# I2C_CH2.net
KiCad netlist of a schematic drawn in Altium Designer
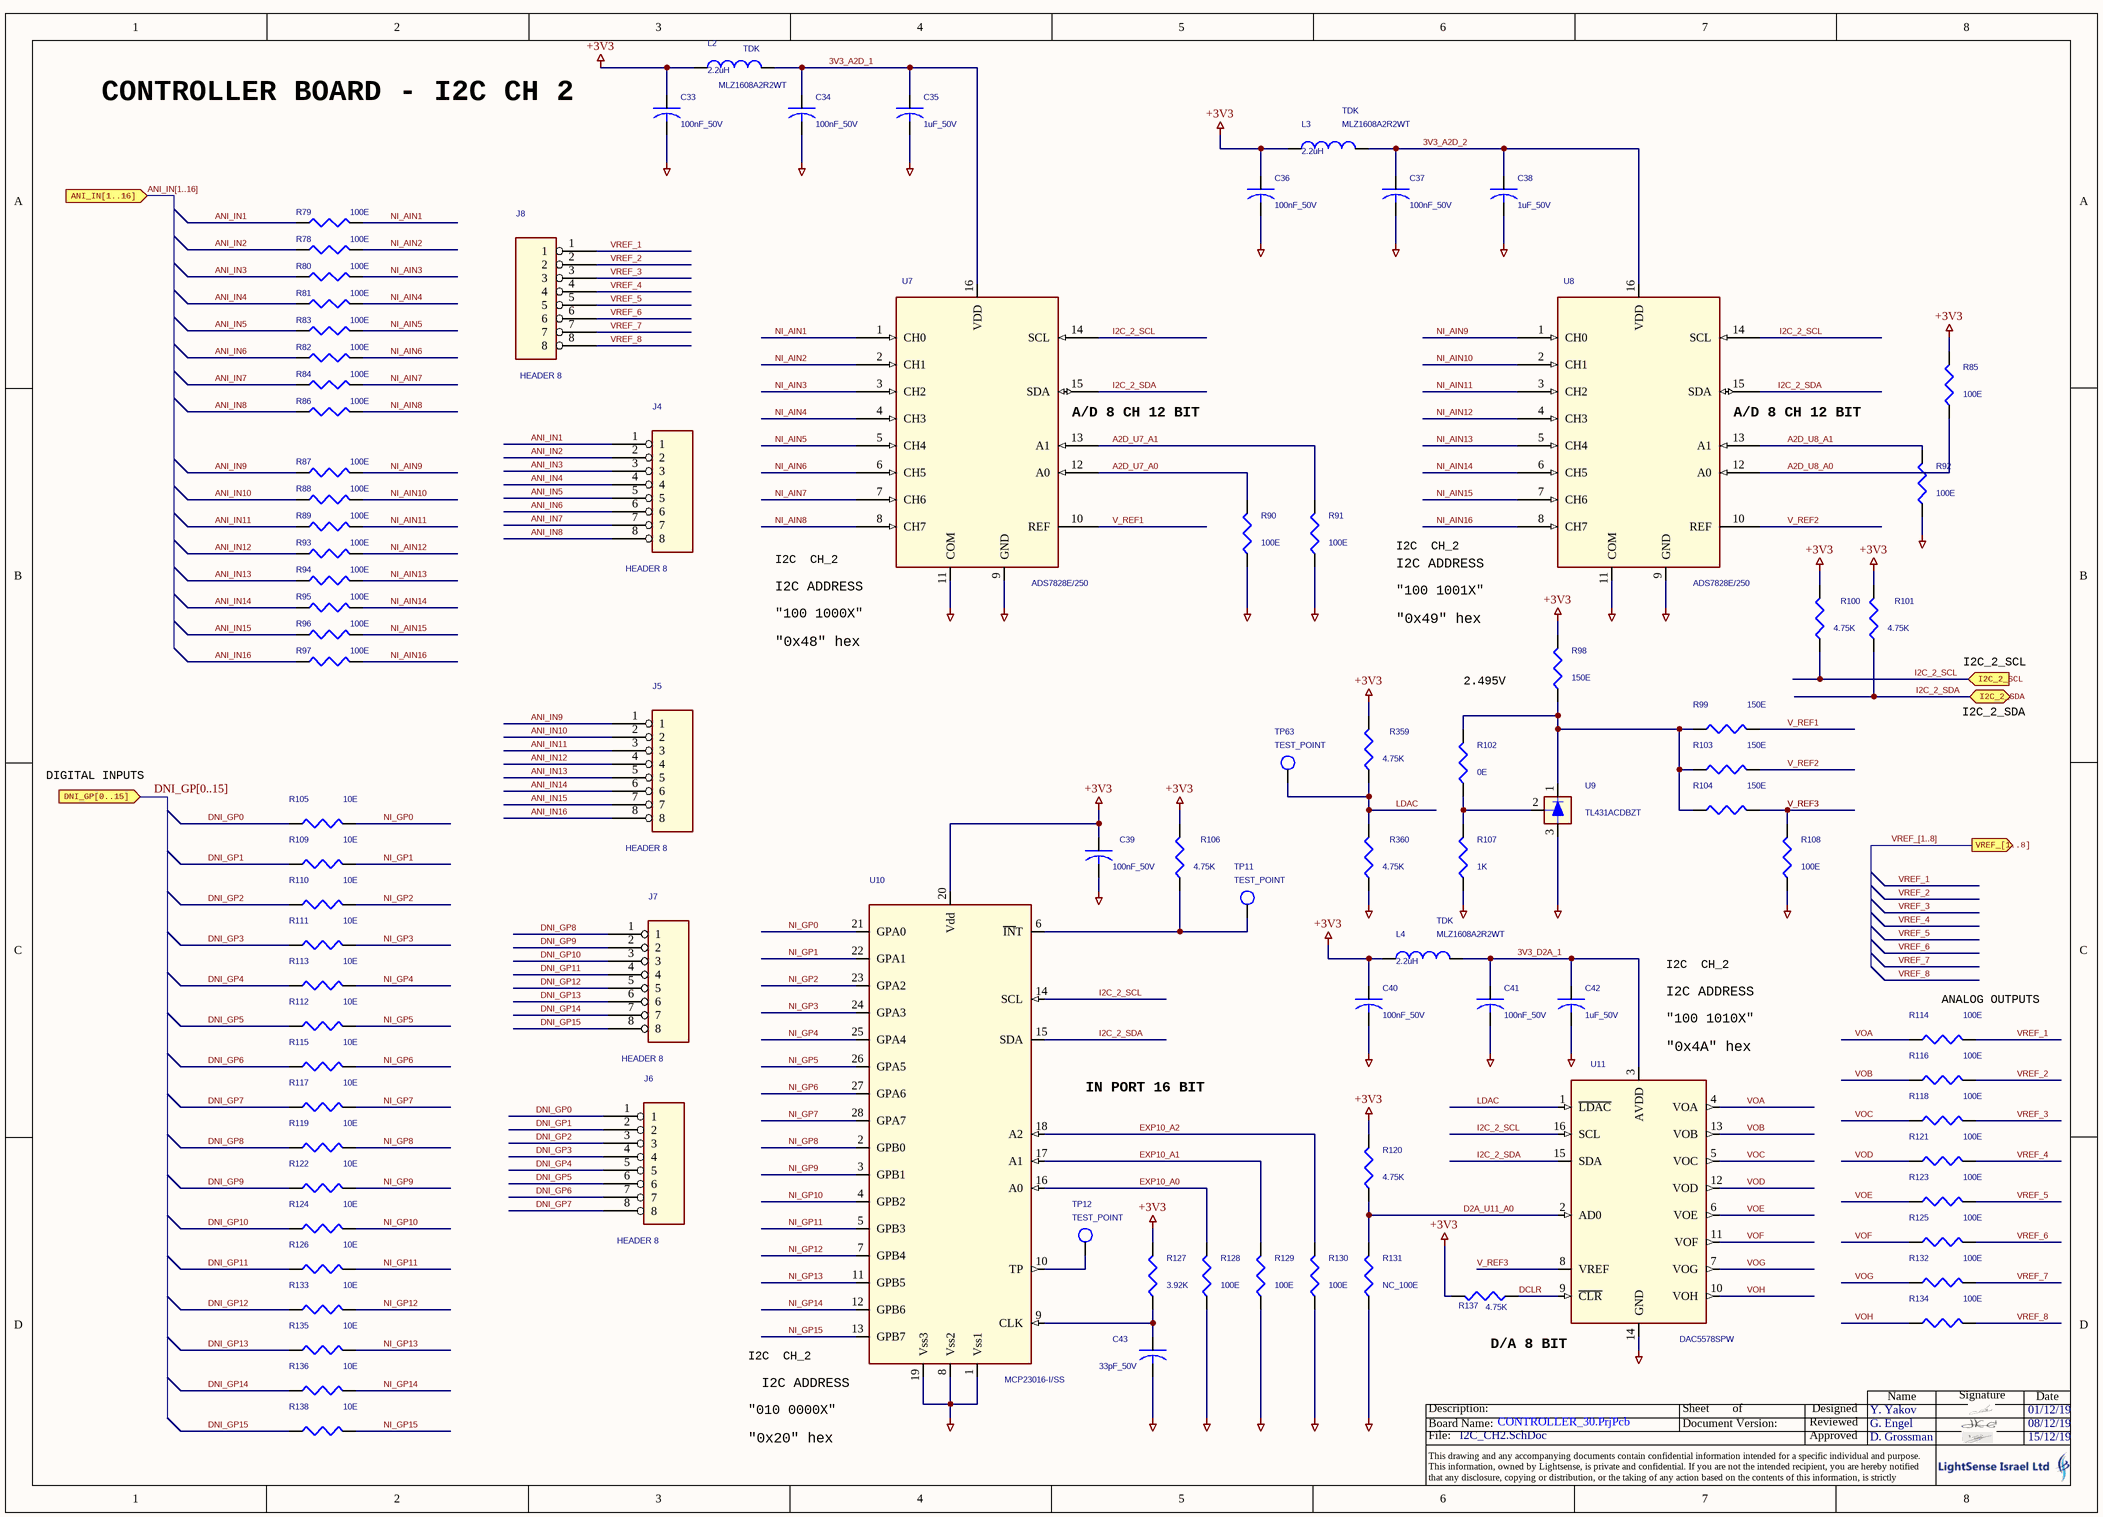
[diagram p0: I2C_CH2.SchDoc]

(export (version "E")
  (design (tool "Eeschema 10.0.6"))
  (components
    (comp (ref "C33")
      (value "100nF_50V")
      (footprint "0603")
      (description "CAP_SMT_0603_50V_X7R_10%")
      (fields (field (name "MFG") "KEMET"))
      (libsource (lib "*") (part "C"))
    )
    (comp (ref "C34")
      (value "100nF_50V")
      (footprint "0603")
      (description "CAP_SMT_0603_50V_X7R_10%")
      (fields (field (name "MFG") "KEMET"))
      (libsource (lib "*") (part "C"))
    )
    (comp (ref "C35")
      (value "1uF_50V")
      (footprint "0805")
      (description "a")
      (fields (field (name "MFG") "Murata") (field (name "MNFCTR_PART_NUMBER") "TCJT106M016R0150"))
      (libsource (lib "*") (part "CAP"))
    )
    (comp (ref "C36")
      (value "100nF_50V")
      (footprint "0603")
      (description "CAP_SMT_0603_50V_X7R_10%")
      (fields (field (name "MFG") "KEMET"))
      (libsource (lib "*") (part "C"))
    )
    (comp (ref "C37")
      (value "100nF_50V")
      (footprint "0603")
      (description "CAP_SMT_0603_50V_X7R_10%")
      (fields (field (name "MFG") "KEMET"))
      (libsource (lib "*") (part "C"))
    )
    (comp (ref "C38")
      (value "1uF_50V")
      (footprint "0805")
      (description "a")
      (fields (field (name "MFG") "Murata") (field (name "MNFCTR_PART_NUMBER") "TCJT106M016R0150"))
      (libsource (lib "*") (part "CAP"))
    )
    (comp (ref "C39")
      (value "100nF_50V")
      (footprint "0603")
      (description "CAP_SMT_0603_50V_X7R_10%")
      (fields (field (name "MFG") "KEMET"))
      (libsource (lib "*") (part "C"))
    )
    (comp (ref "C40")
      (value "100nF_50V")
      (footprint "0603")
      (description "CAP_SMT_0603_50V_X7R_10%")
      (fields (field (name "MFG") "KEMET"))
      (libsource (lib "*") (part "C"))
    )
    (comp (ref "C41")
      (value "100nF_50V")
      (footprint "0603")
      (description "CAP_SMT_0603_50V_X7R_10%")
      (fields (field (name "MFG") "KEMET"))
      (libsource (lib "*") (part "C"))
    )
    (comp (ref "C42")
      (value "1uF_50V")
      (footprint "0805")
      (description "a")
      (fields (field (name "MFG") "Murata") (field (name "MNFCTR_PART_NUMBER") "TCJT106M016R0150"))
      (libsource (lib "*") (part "CAP"))
    )
    (comp (ref "C43")
      (value "33pF_50V")
      (footprint "0603")
      (description "CAP_SMT_0603_50V_X7R_10%")
      (fields (field (name "MFG") "KEMET"))
      (libsource (lib "*") (part "C"))
    )
    (comp (ref "J4") (value "HEADER 8") (footprint "TH_8PIN_100mil") (libsource (lib "") (part "HEADER 8_1")))
    (comp (ref "J5") (value "HEADER 8") (footprint "TH_8PIN_100mil") (libsource (lib "") (part "HEADER 8_1")))
    (comp (ref "J6") (value "HEADER 8") (footprint "TH_8PIN_100mil") (libsource (lib "") (part "HEADER 8_1")))
    (comp (ref "J7") (value "HEADER 8") (footprint "TH_8PIN_100mil") (libsource (lib "") (part "HEADER 8_1")))
    (comp (ref "J8") (value "HEADER 8") (footprint "TH_8PIN_100mil") (libsource (lib "*") (part "HEADER 8")))
    (comp (ref "L2")
      (value "2.2uH")
      (footprint "0603")
      (fields (field (name "MFG") "TDK") (field (name "MFG_PN") "MLZ1608A2R2WT"))
      (libsource (lib "*") (part "INDUCTOR"))
    )
    (comp (ref "L3")
      (value "2.2uH")
      (footprint "0603")
      (fields (field (name "MFG_PN") "MLZ1608A2R2WT") (field (name "MFG") "TDK"))
      (libsource (lib "*") (part "INDUCTOR"))
    )
    (comp (ref "L4")
      (value "2.2uH")
      (footprint "0603")
      (fields (field (name "MFG") "TDK") (field (name "MFG_PN") "MLZ1608A2R2WT"))
      (libsource (lib "*") (part "INDUCTOR"))
    )
    (comp (ref "R78")
      (value "100E")
      (footprint "0603")
      (fields (field (name "MFG") "YAGEO"))
      (libsource (lib "*") (part "R_Dup1"))
    )
    (comp (ref "R79")
      (value "100E")
      (footprint "0603")
      (fields (field (name "MFG") "YAGEO"))
      (libsource (lib "*") (part "R_Dup1"))
    )
    (comp (ref "R80")
      (value "100E")
      (footprint "0603")
      (fields (field (name "MFG") "YAGEO"))
      (libsource (lib "*") (part "R_Dup1"))
    )
    (comp (ref "R81")
      (value "100E")
      (footprint "0603")
      (fields (field (name "MFG") "YAGEO"))
      (libsource (lib "*") (part "R_Dup1"))
    )
    (comp (ref "R82")
      (value "100E")
      (footprint "0603")
      (fields (field (name "MFG") "YAGEO"))
      (libsource (lib "*") (part "R_Dup1"))
    )
    (comp (ref "R83")
      (value "100E")
      (footprint "0603")
      (fields (field (name "MFG") "YAGEO"))
      (libsource (lib "*") (part "R_Dup1"))
    )
    (comp (ref "R84")
      (value "100E")
      (footprint "0603")
      (fields (field (name "MFG") "YAGEO"))
      (libsource (lib "*") (part "R_Dup1"))
    )
    (comp (ref "R85")
      (value "100E")
      (footprint "0603")
      (fields (field (name "MFG") "YAGEO"))
      (libsource (lib "*") (part "R_Dup1"))
    )
    (comp (ref "R86")
      (value "100E")
      (footprint "0603")
      (fields (field (name "MFG") "YAGEO"))
      (libsource (lib "*") (part "R_Dup1"))
    )
    (comp (ref "R87")
      (value "100E")
      (footprint "0603")
      (fields (field (name "MFG") "YAGEO"))
      (libsource (lib "*") (part "R_Dup1"))
    )
    (comp (ref "R88")
      (value "100E")
      (footprint "0603")
      (fields (field (name "MFG") "YAGEO"))
      (libsource (lib "*") (part "R_Dup1"))
    )
    (comp (ref "R89")
      (value "100E")
      (footprint "0603")
      (fields (field (name "MFG") "YAGEO"))
      (libsource (lib "*") (part "R_Dup1"))
    )
    (comp (ref "R90")
      (value "100E")
      (footprint "0603")
      (fields (field (name "MFG") "YAGEO"))
      (libsource (lib "*") (part "R_Dup1"))
    )
    (comp (ref "R91")
      (value "100E")
      (footprint "0603")
      (fields (field (name "MFG") "YAGEO"))
      (libsource (lib "*") (part "R_Dup1"))
    )
    (comp (ref "R92")
      (value "100E")
      (footprint "0603")
      (fields (field (name "MFG") "YAGEO"))
      (libsource (lib "*") (part "R_Dup1"))
    )
    (comp (ref "R93")
      (value "100E")
      (footprint "0603")
      (fields (field (name "MFG") "YAGEO"))
      (libsource (lib "*") (part "R_Dup1"))
    )
    (comp (ref "R94")
      (value "100E")
      (footprint "0603")
      (fields (field (name "MFG") "YAGEO"))
      (libsource (lib "*") (part "R_Dup1"))
    )
    (comp (ref "R95")
      (value "100E")
      (footprint "0603")
      (fields (field (name "MFG") "YAGEO"))
      (libsource (lib "*") (part "R_Dup1"))
    )
    (comp (ref "R96")
      (value "100E")
      (footprint "0603")
      (fields (field (name "MFG") "YAGEO"))
      (libsource (lib "*") (part "R_Dup1"))
    )
    (comp (ref "R97")
      (value "100E")
      (footprint "0603")
      (fields (field (name "MFG") "YAGEO"))
      (libsource (lib "*") (part "R_Dup1"))
    )
    (comp (ref "R98")
      (value "150E")
      (footprint "0603")
      (fields (field (name "MFG") "YAGEO"))
      (libsource (lib "*") (part "R_Dup1"))
    )
    (comp (ref "R99")
      (value "150E")
      (footprint "0603")
      (fields (field (name "MFG") "YAGEO"))
      (libsource (lib "*") (part "R_Dup1"))
    )
    (comp (ref "R100")
      (value "4.75K")
      (footprint "0603")
      (fields (field (name "MFG") "YAGEO"))
      (libsource (lib "*") (part "R_Dup1"))
    )
    (comp (ref "R101")
      (value "4.75K")
      (footprint "0603")
      (fields (field (name "MFG") "YAGEO"))
      (libsource (lib "*") (part "R_Dup1"))
    )
    (comp (ref "R102")
      (value "0E")
      (footprint "0603")
      (fields (field (name "MFG") "YAGEO"))
      (libsource (lib "*") (part "R_Dup1"))
    )
    (comp (ref "R103")
      (value "150E")
      (footprint "0603")
      (fields (field (name "MFG") "YAGEO"))
      (libsource (lib "*") (part "R_Dup1"))
    )
    (comp (ref "R104")
      (value "150E")
      (footprint "0603")
      (fields (field (name "MFG") "YAGEO"))
      (libsource (lib "*") (part "R_Dup1"))
    )
    (comp (ref "R105")
      (value "10E")
      (footprint "0603")
      (fields (field (name "MFG") "YAGEO"))
      (libsource (lib "*") (part "R_Dup1"))
    )
    (comp (ref "R106")
      (value "4.75K")
      (footprint "0603")
      (fields (field (name "MFG") "YAGEO"))
      (libsource (lib "*") (part "R_Dup1"))
    )
    (comp (ref "R107")
      (value "1K")
      (footprint "0603")
      (fields (field (name "MFG") "YAGEO"))
      (libsource (lib "*") (part "R_Dup1"))
    )
    (comp (ref "R108")
      (value "100E")
      (footprint "0603")
      (fields (field (name "MFG") "YAGEO"))
      (libsource (lib "*") (part "R_Dup1"))
    )
    (comp (ref "R109")
      (value "10E")
      (footprint "0603")
      (fields (field (name "MFG") "YAGEO"))
      (libsource (lib "*") (part "R_Dup1"))
    )
    (comp (ref "R110")
      (value "10E")
      (footprint "0603")
      (fields (field (name "MFG") "YAGEO"))
      (libsource (lib "*") (part "R_Dup1"))
    )
    (comp (ref "R111")
      (value "10E")
      (footprint "0603")
      (fields (field (name "MFG") "YAGEO"))
      (libsource (lib "*") (part "R_Dup1"))
    )
    (comp (ref "R112")
      (value "10E")
      (footprint "0603")
      (fields (field (name "MFG") "YAGEO"))
      (libsource (lib "*") (part "R_Dup1"))
    )
    (comp (ref "R113")
      (value "10E")
      (footprint "0603")
      (fields (field (name "MFG") "YAGEO"))
      (libsource (lib "*") (part "R_Dup1"))
    )
    (comp (ref "R114")
      (value "100E")
      (footprint "0603")
      (fields (field (name "MFG") "YAGEO"))
      (libsource (lib "*") (part "R_Dup1"))
    )
    (comp (ref "R115")
      (value "10E")
      (footprint "0603")
      (fields (field (name "MFG") "YAGEO"))
      (libsource (lib "*") (part "R_Dup1"))
    )
    (comp (ref "R116")
      (value "100E")
      (footprint "0603")
      (fields (field (name "MFG") "YAGEO"))
      (libsource (lib "*") (part "R_Dup1"))
    )
    (comp (ref "R117")
      (value "10E")
      (footprint "0603")
      (fields (field (name "MFG") "YAGEO"))
      (libsource (lib "*") (part "R_Dup1"))
    )
    (comp (ref "R118")
      (value "100E")
      (footprint "0603")
      (fields (field (name "MFG") "YAGEO"))
      (libsource (lib "*") (part "R_Dup1"))
    )
    (comp (ref "R119")
      (value "10E")
      (footprint "0603")
      (fields (field (name "MFG") "YAGEO"))
      (libsource (lib "*") (part "R_Dup1"))
    )
    (comp (ref "R120")
      (value "4.75K")
      (footprint "0603")
      (fields (field (name "MFG") "YAGEO"))
      (libsource (lib "*") (part "R_Dup1"))
    )
    (comp (ref "R121")
      (value "100E")
      (footprint "0603")
      (fields (field (name "MFG") "YAGEO"))
      (libsource (lib "*") (part "R_Dup1"))
    )
    (comp (ref "R122")
      (value "10E")
      (footprint "0603")
      (fields (field (name "MFG") "YAGEO"))
      (libsource (lib "*") (part "R_Dup1"))
    )
    (comp (ref "R123")
      (value "100E")
      (footprint "0603")
      (fields (field (name "MFG") "YAGEO"))
      (libsource (lib "*") (part "R_Dup1"))
    )
    (comp (ref "R124")
      (value "10E")
      (footprint "0603")
      (fields (field (name "MFG") "YAGEO"))
      (libsource (lib "*") (part "R_Dup1"))
    )
    (comp (ref "R125")
      (value "100E")
      (footprint "0603")
      (fields (field (name "MFG") "YAGEO"))
      (libsource (lib "*") (part "R_Dup1"))
    )
    (comp (ref "R126")
      (value "10E")
      (footprint "0603")
      (fields (field (name "MFG") "YAGEO"))
      (libsource (lib "*") (part "R_Dup1"))
    )
    (comp (ref "R127")
      (value "3.92K")
      (footprint "0603")
      (fields (field (name "MFG") "YAGEO"))
      (libsource (lib "*") (part "R_Dup1"))
    )
    (comp (ref "R128")
      (value "100E")
      (footprint "0603")
      (fields (field (name "MFG") "YAGEO"))
      (libsource (lib "*") (part "R_Dup1"))
    )
    (comp (ref "R129")
      (value "100E")
      (footprint "0603")
      (fields (field (name "MFG") "YAGEO"))
      (libsource (lib "*") (part "R_Dup1"))
    )
    (comp (ref "R130")
      (value "100E")
      (footprint "0603")
      (fields (field (name "MFG") "YAGEO"))
      (libsource (lib "*") (part "R_Dup1"))
    )
    (comp (ref "R131")
      (value "NC_100E")
      (footprint "0603")
      (fields (field (name "MFG") "YAGEO"))
      (libsource (lib "*") (part "R_Dup1"))
    )
    (comp (ref "R132")
      (value "100E")
      (footprint "0603")
      (fields (field (name "MFG") "YAGEO"))
      (libsource (lib "*") (part "R_Dup1"))
    )
    (comp (ref "R133")
      (value "10E")
      (footprint "0603")
      (fields (field (name "MFG") "YAGEO"))
      (libsource (lib "*") (part "R_Dup1"))
    )
    (comp (ref "R134")
      (value "100E")
      (footprint "0603")
      (fields (field (name "MFG") "YAGEO"))
      (libsource (lib "*") (part "R_Dup1"))
    )
    (comp (ref "R135")
      (value "10E")
      (footprint "0603")
      (fields (field (name "MFG") "YAGEO"))
      (libsource (lib "*") (part "R_Dup1"))
    )
    (comp (ref "R136")
      (value "10E")
      (footprint "0603")
      (fields (field (name "MFG") "YAGEO"))
      (libsource (lib "*") (part "R_Dup1"))
    )
    (comp (ref "R137")
      (value "4.75K")
      (footprint "0603")
      (fields (field (name "MFG") "YAGEO"))
      (libsource (lib "*") (part "R_Dup1"))
    )
    (comp (ref "R138")
      (value "10E")
      (footprint "0603")
      (fields (field (name "MFG") "YAGEO"))
      (libsource (lib "*") (part "R_Dup1"))
    )
    (comp (ref "R359")
      (value "4.75K")
      (footprint "0603")
      (fields (field (name "MFG") "YAGEO"))
      (libsource (lib "*") (part "R_Dup1"))
    )
    (comp (ref "R360")
      (value "4.75K")
      (footprint "0603")
      (fields (field (name "MFG") "YAGEO"))
      (libsource (lib "*") (part "R_Dup1"))
    )
    (comp (ref "TP11")
      (value "TEST_POINT")
      (footprint "TH_1mm")
      (libsource (lib "*") (part "T POINT R_Dup1"))
    )
    (comp (ref "TP12")
      (value "TEST_POINT")
      (footprint "TH_1mm")
      (libsource (lib "*") (part "T POINT R_Dup1"))
    )
    (comp (ref "TP63")
      (value "TEST_POINT")
      (footprint "TH_1mm")
      (libsource (lib "*") (part "T POINT R_Dup1"))
    )
    (comp (ref "U7")
      (value "ADS7828E/250")
      (footprint "TSSOP_16")
      (fields (field (name "MFG") "TI"))
      (libsource (lib "*") (part "ADS7828E"))
    )
    (comp (ref "U8")
      (value "ADS7828E/250")
      (footprint "TSSOP_16")
      (fields (field (name "MFG") "TI"))
      (libsource (lib "*") (part "ADS7828E"))
    )
    (comp (ref "U9")
      (value "TL431ACDBZT")
      (footprint "SOT_23")
      (fields (field (name "PART_NUMBER") "<Part_Number>") (field (name "MFG") "TI"))
      (libsource (lib "*") (part "TL431ACDBZT"))
    )
    (comp (ref "U10")
      (value "MCP23016-I/SS")
      (footprint "SSOP_28")
      (fields (field (name "MFG") "MICROCHIP"))
      (libsource (lib "*") (part "MCP23016-I/SS"))
    )
    (comp (ref "U11")
      (value "DAC5578SPW")
      (footprint "TSSOP_16")
      (fields (field (name "MFG") "TI"))
      (libsource (lib "*") (part "DAC5578SPW"))
    )
  )
  (nets
    (net (code "1") (name "+3V3") (class "Default")
      (node (ref "C33") (pin "1") (pinfunction "1_1") (pintype "passive"))
      (node (ref "C36") (pin "1") (pinfunction "1_1") (pintype "passive"))
      (node (ref "C39") (pin "1") (pinfunction "1_1") (pintype "passive"))
      (node (ref "C40") (pin "1") (pinfunction "1_1") (pintype "passive"))
      (node (ref "L2") (pin "1") (pinfunction "1_1") (pintype "passive"))
      (node (ref "L3") (pin "1") (pinfunction "1_1") (pintype "passive"))
      (node (ref "L4") (pin "1") (pinfunction "1_1") (pintype "passive"))
      (node (ref "R100") (pin "2") (pinfunction "2_2") (pintype "passive"))
      (node (ref "R101") (pin "2") (pinfunction "2_2") (pintype "passive"))
      (node (ref "R106") (pin "2") (pinfunction "2_2") (pintype "passive"))
      (node (ref "R120") (pin "2") (pinfunction "2_2") (pintype "passive"))
      (node (ref "R127") (pin "2") (pinfunction "2_2") (pintype "passive"))
      (node (ref "R137") (pin "2") (pinfunction "2_2") (pintype "passive"))
      (node (ref "R359") (pin "2") (pinfunction "2_2") (pintype "passive"))
      (node (ref "R85") (pin "2") (pinfunction "2_2") (pintype "passive"))
      (node (ref "R98") (pin "2") (pinfunction "2_2") (pintype "passive"))
      (node (ref "U10") (pin "20") (pinfunction "Vdd_20") (pintype "passive"))
    )
    (net (code "2") (name "/3V3_A2D_1") (class "Default")
      (node (ref "C34") (pin "1") (pinfunction "1_1") (pintype "passive"))
      (node (ref "C35") (pin "1") (pinfunction "1_1") (pintype "passive"))
      (node (ref "L2") (pin "2") (pinfunction "2_2") (pintype "passive"))
      (node (ref "U7") (pin "16") (pinfunction "VDD_16") (pintype "passive"))
    )
    (net (code "3") (name "/3V3_A2D_2") (class "Default")
      (node (ref "C37") (pin "1") (pinfunction "1_1") (pintype "passive"))
      (node (ref "C38") (pin "1") (pinfunction "1_1") (pintype "passive"))
      (node (ref "L3") (pin "2") (pinfunction "2_2") (pintype "passive"))
      (node (ref "U8") (pin "16") (pinfunction "VDD_16") (pintype "passive"))
    )
    (net (code "4") (name "/3V3_D2A_1") (class "Default")
      (node (ref "C41") (pin "1") (pinfunction "1_1") (pintype "passive"))
      (node (ref "C42") (pin "1") (pinfunction "1_1") (pintype "passive"))
      (node (ref "L4") (pin "2") (pinfunction "2_2") (pintype "passive"))
      (node (ref "U11") (pin "3") (pinfunction "AVDD_3") (pintype "passive"))
    )
    (net (code "5") (name "/A2D_U7_A0") (class "Default")
      (node (ref "R90") (pin "2") (pinfunction "2_2") (pintype "passive"))
      (node (ref "U7") (pin "12") (pinfunction "A0_12") (pintype "input"))
    )
    (net (code "6") (name "/A2D_U7_A1") (class "Default")
      (node (ref "R91") (pin "2") (pinfunction "2_2") (pintype "passive"))
      (node (ref "U7") (pin "13") (pinfunction "A1_13") (pintype "input"))
    )
    (net (code "7") (name "/A2D_U8_A0") (class "Default")
      (node (ref "R85") (pin "1") (pinfunction "1_1") (pintype "passive"))
      (node (ref "U8") (pin "12") (pinfunction "A0_12") (pintype "input"))
    )
    (net (code "8") (name "/A2D_U8_A1") (class "Default")
      (node (ref "R92") (pin "2") (pinfunction "2_2") (pintype "passive"))
      (node (ref "U8") (pin "13") (pinfunction "A1_13") (pintype "input"))
    )
    (net (code "9") (name "/ANI_IN1") (class "Default")
      (node (ref "J4") (pin "1") (pinfunction "1_1") (pintype "passive"))
      (node (ref "R79") (pin "2") (pinfunction "2_2") (pintype "passive"))
    )
    (net (code "10") (name "/ANI_IN2") (class "Default")
      (node (ref "J4") (pin "2") (pinfunction "2_2") (pintype "passive"))
      (node (ref "R78") (pin "2") (pinfunction "2_2") (pintype "passive"))
    )
    (net (code "11") (name "/ANI_IN3") (class "Default")
      (node (ref "J4") (pin "3") (pinfunction "3_3") (pintype "passive"))
      (node (ref "R80") (pin "2") (pinfunction "2_2") (pintype "passive"))
    )
    (net (code "12") (name "/ANI_IN4") (class "Default")
      (node (ref "J4") (pin "4") (pinfunction "4_4") (pintype "passive"))
      (node (ref "R81") (pin "2") (pinfunction "2_2") (pintype "passive"))
    )
    (net (code "13") (name "/ANI_IN5") (class "Default")
      (node (ref "J4") (pin "5") (pinfunction "5_5") (pintype "passive"))
      (node (ref "R83") (pin "2") (pinfunction "2_2") (pintype "passive"))
    )
    (net (code "14") (name "/ANI_IN6") (class "Default")
      (node (ref "J4") (pin "6") (pinfunction "6_6") (pintype "passive"))
      (node (ref "R82") (pin "2") (pinfunction "2_2") (pintype "passive"))
    )
    (net (code "15") (name "/ANI_IN7") (class "Default")
      (node (ref "J4") (pin "7") (pinfunction "7_7") (pintype "passive"))
      (node (ref "R84") (pin "2") (pinfunction "2_2") (pintype "passive"))
    )
    (net (code "16") (name "/ANI_IN8") (class "Default")
      (node (ref "J4") (pin "8") (pinfunction "8_8") (pintype "passive"))
      (node (ref "R86") (pin "2") (pinfunction "2_2") (pintype "passive"))
    )
    (net (code "17") (name "/ANI_IN9") (class "Default")
      (node (ref "J5") (pin "1") (pinfunction "1_1") (pintype "passive"))
      (node (ref "R87") (pin "2") (pinfunction "2_2") (pintype "passive"))
    )
    (net (code "18") (name "/ANI_IN10") (class "Default")
      (node (ref "J5") (pin "2") (pinfunction "2_2") (pintype "passive"))
      (node (ref "R88") (pin "2") (pinfunction "2_2") (pintype "passive"))
    )
    (net (code "19") (name "/ANI_IN11") (class "Default")
      (node (ref "J5") (pin "3") (pinfunction "3_3") (pintype "passive"))
      (node (ref "R89") (pin "2") (pinfunction "2_2") (pintype "passive"))
    )
    (net (code "20") (name "/ANI_IN12") (class "Default")
      (node (ref "J5") (pin "4") (pinfunction "4_4") (pintype "passive"))
      (node (ref "R93") (pin "2") (pinfunction "2_2") (pintype "passive"))
    )
    (net (code "21") (name "/ANI_IN13") (class "Default")
      (node (ref "J5") (pin "5") (pinfunction "5_5") (pintype "passive"))
      (node (ref "R94") (pin "2") (pinfunction "2_2") (pintype "passive"))
    )
    (net (code "22") (name "/ANI_IN14") (class "Default")
      (node (ref "J5") (pin "6") (pinfunction "6_6") (pintype "passive"))
      (node (ref "R95") (pin "2") (pinfunction "2_2") (pintype "passive"))
    )
    (net (code "23") (name "/ANI_IN15") (class "Default")
      (node (ref "J5") (pin "7") (pinfunction "7_7") (pintype "passive"))
      (node (ref "R96") (pin "2") (pinfunction "2_2") (pintype "passive"))
    )
    (net (code "24") (name "/ANI_IN16") (class "Default")
      (node (ref "J5") (pin "8") (pinfunction "8_8") (pintype "passive"))
      (node (ref "R97") (pin "2") (pinfunction "2_2") (pintype "passive"))
    )
    (net (code "26") (name "/D2A_U11_A0") (class "Default")
      (node (ref "R120") (pin "1") (pinfunction "1_1") (pintype "passive"))
      (node (ref "R131") (pin "2") (pinfunction "2_2") (pintype "passive"))
      (node (ref "U11") (pin "2") (pinfunction "AD0_2") (pintype "input"))
    )
    (net (code "27") (name "/DCLR") (class "Default")
      (node (ref "R137") (pin "1") (pinfunction "1_1") (pintype "passive"))
      (node (ref "U11") (pin "9") (pinfunction "~{CLR}_9") (pintype "input"))
    )
    (net (code "28") (name "/DNI_GP0") (class "Default")
      (node (ref "J6") (pin "1") (pinfunction "1_1") (pintype "passive"))
      (node (ref "R105") (pin "2") (pinfunction "2_2") (pintype "passive"))
    )
    (net (code "29") (name "/DNI_GP1") (class "Default")
      (node (ref "J6") (pin "2") (pinfunction "2_2") (pintype "passive"))
      (node (ref "R109") (pin "2") (pinfunction "2_2") (pintype "passive"))
    )
    (net (code "30") (name "/DNI_GP2") (class "Default")
      (node (ref "J6") (pin "3") (pinfunction "3_3") (pintype "passive"))
      (node (ref "R110") (pin "2") (pinfunction "2_2") (pintype "passive"))
    )
    (net (code "31") (name "/DNI_GP3") (class "Default")
      (node (ref "J6") (pin "4") (pinfunction "4_4") (pintype "passive"))
      (node (ref "R111") (pin "2") (pinfunction "2_2") (pintype "passive"))
    )
    (net (code "32") (name "/DNI_GP4") (class "Default")
      (node (ref "J6") (pin "5") (pinfunction "5_5") (pintype "passive"))
      (node (ref "R113") (pin "2") (pinfunction "2_2") (pintype "passive"))
    )
    (net (code "33") (name "/DNI_GP5") (class "Default")
      (node (ref "J6") (pin "6") (pinfunction "6_6") (pintype "passive"))
      (node (ref "R112") (pin "2") (pinfunction "2_2") (pintype "passive"))
    )
    (net (code "34") (name "/DNI_GP6") (class "Default")
      (node (ref "J6") (pin "7") (pinfunction "7_7") (pintype "passive"))
      (node (ref "R115") (pin "2") (pinfunction "2_2") (pintype "passive"))
    )
    (net (code "35") (name "/DNI_GP7") (class "Default")
      (node (ref "J6") (pin "8") (pinfunction "8_8") (pintype "passive"))
      (node (ref "R117") (pin "2") (pinfunction "2_2") (pintype "passive"))
    )
    (net (code "36") (name "/DNI_GP8") (class "Default")
      (node (ref "J7") (pin "1") (pinfunction "1_1") (pintype "passive"))
      (node (ref "R119") (pin "2") (pinfunction "2_2") (pintype "passive"))
    )
    (net (code "37") (name "/DNI_GP9") (class "Default")
      (node (ref "J7") (pin "2") (pinfunction "2_2") (pintype "passive"))
      (node (ref "R122") (pin "2") (pinfunction "2_2") (pintype "passive"))
    )
    (net (code "38") (name "/DNI_GP10") (class "Default")
      (node (ref "J7") (pin "3") (pinfunction "3_3") (pintype "passive"))
      (node (ref "R124") (pin "2") (pinfunction "2_2") (pintype "passive"))
    )
    (net (code "39") (name "/DNI_GP11") (class "Default")
      (node (ref "J7") (pin "4") (pinfunction "4_4") (pintype "passive"))
      (node (ref "R126") (pin "2") (pinfunction "2_2") (pintype "passive"))
    )
    (net (code "40") (name "/DNI_GP12") (class "Default")
      (node (ref "J7") (pin "5") (pinfunction "5_5") (pintype "passive"))
      (node (ref "R133") (pin "2") (pinfunction "2_2") (pintype "passive"))
    )
    (net (code "41") (name "/DNI_GP13") (class "Default")
      (node (ref "J7") (pin "6") (pinfunction "6_6") (pintype "passive"))
      (node (ref "R135") (pin "2") (pinfunction "2_2") (pintype "passive"))
    )
    (net (code "42") (name "/DNI_GP14") (class "Default")
      (node (ref "J7") (pin "7") (pinfunction "7_7") (pintype "passive"))
      (node (ref "R136") (pin "2") (pinfunction "2_2") (pintype "passive"))
    )
    (net (code "43") (name "/DNI_GP15") (class "Default")
      (node (ref "J7") (pin "8") (pinfunction "8_8") (pintype "passive"))
      (node (ref "R138") (pin "2") (pinfunction "2_2") (pintype "passive"))
    )
    (net (code "45") (name "/EXP10_A0") (class "Default")
      (node (ref "R128") (pin "2") (pinfunction "2_2") (pintype "passive"))
      (node (ref "U10") (pin "16") (pinfunction "A0_16") (pintype "input"))
    )
    (net (code "46") (name "/EXP10_A1") (class "Default")
      (node (ref "R129") (pin "2") (pinfunction "2_2") (pintype "passive"))
      (node (ref "U10") (pin "17") (pinfunction "A1_17") (pintype "input"))
    )
    (net (code "47") (name "/EXP10_A2") (class "Default")
      (node (ref "R130") (pin "2") (pinfunction "2_2") (pintype "passive"))
      (node (ref "U10") (pin "18") (pinfunction "A2_18") (pintype "input"))
    )
    (net (code "48") (name "/I2C_2_SCL") (class "Default")
      (node (ref "R100") (pin "1") (pinfunction "1_1") (pintype "passive"))
      (node (ref "U10") (pin "14") (pinfunction "SCL_14") (pintype "input"))
      (node (ref "U11") (pin "16") (pinfunction "SCL_16") (pintype "input"))
      (node (ref "U7") (pin "14") (pinfunction "SCL_14") (pintype "input"))
      (node (ref "U8") (pin "14") (pinfunction "SCL_14") (pintype "input"))
    )
    (net (code "49") (name "/I2C_2_SDA") (class "Default")
      (node (ref "R101") (pin "1") (pinfunction "1_1") (pintype "passive"))
      (node (ref "U10") (pin "15") (pinfunction "SDA_15") (pintype "bidirectional"))
      (node (ref "U11") (pin "15") (pinfunction "SDA_15") (pintype "bidirectional"))
      (node (ref "U7") (pin "15") (pinfunction "SDA_15") (pintype "bidirectional"))
      (node (ref "U8") (pin "15") (pinfunction "SDA_15") (pintype "bidirectional"))
    )
    (net (code "50") (name "/LDAC") (class "Default")
      (node (ref "R359") (pin "1") (pinfunction "1_1") (pintype "passive"))
      (node (ref "R360") (pin "2") (pinfunction "2_2") (pintype "passive"))
      (node (ref "TP63") (pin "1") (pinfunction "TP_1") (pintype "passive"))
      (node (ref "U11") (pin "1") (pinfunction "~{LDAC}_1") (pintype "input"))
    )
    (net (code "51") (name "/NI_AIN1") (class "Default")
      (node (ref "R79") (pin "1") (pinfunction "1_1") (pintype "passive"))
      (node (ref "U7") (pin "1") (pinfunction "CH0_1") (pintype "input"))
    )
    (net (code "52") (name "/NI_AIN2") (class "Default")
      (node (ref "R78") (pin "1") (pinfunction "1_1") (pintype "passive"))
      (node (ref "U7") (pin "2") (pinfunction "CH1_2") (pintype "input"))
    )
    (net (code "53") (name "/NI_AIN3") (class "Default")
      (node (ref "R80") (pin "1") (pinfunction "1_1") (pintype "passive"))
      (node (ref "U7") (pin "3") (pinfunction "CH2_3") (pintype "input"))
    )
    (net (code "54") (name "/NI_AIN4") (class "Default")
      (node (ref "R81") (pin "1") (pinfunction "1_1") (pintype "passive"))
      (node (ref "U7") (pin "4") (pinfunction "CH3_4") (pintype "input"))
    )
    (net (code "55") (name "/NI_AIN5") (class "Default")
      (node (ref "R83") (pin "1") (pinfunction "1_1") (pintype "passive"))
      (node (ref "U7") (pin "5") (pinfunction "CH4_5") (pintype "input"))
    )
    (net (code "56") (name "/NI_AIN6") (class "Default")
      (node (ref "R82") (pin "1") (pinfunction "1_1") (pintype "passive"))
      (node (ref "U7") (pin "6") (pinfunction "CH5_6") (pintype "input"))
    )
    (net (code "57") (name "/NI_AIN7") (class "Default")
      (node (ref "R84") (pin "1") (pinfunction "1_1") (pintype "passive"))
      (node (ref "U7") (pin "7") (pinfunction "CH6_7") (pintype "input"))
    )
    (net (code "58") (name "/NI_AIN8") (class "Default")
      (node (ref "R86") (pin "1") (pinfunction "1_1") (pintype "passive"))
      (node (ref "U7") (pin "8") (pinfunction "CH7_8") (pintype "input"))
    )
    (net (code "59") (name "/NI_AIN9") (class "Default")
      (node (ref "R87") (pin "1") (pinfunction "1_1") (pintype "passive"))
      (node (ref "U8") (pin "1") (pinfunction "CH0_1") (pintype "input"))
    )
    (net (code "60") (name "/NI_AIN10") (class "Default")
      (node (ref "R88") (pin "1") (pinfunction "1_1") (pintype "passive"))
      (node (ref "U8") (pin "2") (pinfunction "CH1_2") (pintype "input"))
    )
    (net (code "61") (name "/NI_AIN11") (class "Default")
      (node (ref "R89") (pin "1") (pinfunction "1_1") (pintype "passive"))
      (node (ref "U8") (pin "3") (pinfunction "CH2_3") (pintype "input"))
    )
    (net (code "62") (name "/NI_AIN12") (class "Default")
      (node (ref "R93") (pin "1") (pinfunction "1_1") (pintype "passive"))
      (node (ref "U8") (pin "4") (pinfunction "CH3_4") (pintype "input"))
    )
    (net (code "63") (name "/NI_AIN13") (class "Default")
      (node (ref "R94") (pin "1") (pinfunction "1_1") (pintype "passive"))
      (node (ref "U8") (pin "5") (pinfunction "CH4_5") (pintype "input"))
    )
    (net (code "64") (name "/NI_AIN14") (class "Default")
      (node (ref "R95") (pin "1") (pinfunction "1_1") (pintype "passive"))
      (node (ref "U8") (pin "6") (pinfunction "CH5_6") (pintype "input"))
    )
    (net (code "65") (name "/NI_AIN15") (class "Default")
      (node (ref "R96") (pin "1") (pinfunction "1_1") (pintype "passive"))
      (node (ref "U8") (pin "7") (pinfunction "CH6_7") (pintype "input"))
    )
    (net (code "66") (name "/NI_AIN16") (class "Default")
      (node (ref "R97") (pin "1") (pinfunction "1_1") (pintype "passive"))
      (node (ref "U8") (pin "8") (pinfunction "CH7_8") (pintype "input"))
    )
    (net (code "67") (name "/NI_GP0") (class "Default")
      (node (ref "R105") (pin "1") (pinfunction "1_1") (pintype "passive"))
      (node (ref "U10") (pin "21") (pinfunction "GPA0_21") (pintype "bidirectional"))
    )
    (net (code "68") (name "/NI_GP1") (class "Default")
      (node (ref "R109") (pin "1") (pinfunction "1_1") (pintype "passive"))
      (node (ref "U10") (pin "22") (pinfunction "GPA1_22") (pintype "bidirectional"))
    )
    (net (code "69") (name "/NI_GP2") (class "Default")
      (node (ref "R110") (pin "1") (pinfunction "1_1") (pintype "passive"))
      (node (ref "U10") (pin "23") (pinfunction "GPA2_23") (pintype "bidirectional"))
    )
    (net (code "70") (name "/NI_GP3") (class "Default")
      (node (ref "R111") (pin "1") (pinfunction "1_1") (pintype "passive"))
      (node (ref "U10") (pin "24") (pinfunction "GPA3_24") (pintype "bidirectional"))
    )
    (net (code "71") (name "/NI_GP4") (class "Default")
      (node (ref "R113") (pin "1") (pinfunction "1_1") (pintype "passive"))
      (node (ref "U10") (pin "25") (pinfunction "GPA4_25") (pintype "bidirectional"))
    )
    (net (code "72") (name "/NI_GP5") (class "Default")
      (node (ref "R112") (pin "1") (pinfunction "1_1") (pintype "passive"))
      (node (ref "U10") (pin "26") (pinfunction "GPA5_26") (pintype "bidirectional"))
    )
    (net (code "73") (name "/NI_GP6") (class "Default")
      (node (ref "R115") (pin "1") (pinfunction "1_1") (pintype "passive"))
      (node (ref "U10") (pin "27") (pinfunction "GPA6_27") (pintype "bidirectional"))
    )
    (net (code "74") (name "/NI_GP7") (class "Default")
      (node (ref "R117") (pin "1") (pinfunction "1_1") (pintype "passive"))
      (node (ref "U10") (pin "28") (pinfunction "GPA7_28") (pintype "bidirectional"))
    )
    (net (code "75") (name "/NI_GP8") (class "Default")
      (node (ref "R119") (pin "1") (pinfunction "1_1") (pintype "passive"))
      (node (ref "U10") (pin "2") (pinfunction "GPB0_2") (pintype "bidirectional"))
    )
    (net (code "76") (name "/NI_GP9") (class "Default")
      (node (ref "R122") (pin "1") (pinfunction "1_1") (pintype "passive"))
      (node (ref "U10") (pin "3") (pinfunction "GPB1_3") (pintype "bidirectional"))
    )
    (net (code "77") (name "/NI_GP10") (class "Default")
      (node (ref "R124") (pin "1") (pinfunction "1_1") (pintype "passive"))
      (node (ref "U10") (pin "4") (pinfunction "GPB2_4") (pintype "bidirectional"))
    )
    (net (code "78") (name "/NI_GP11") (class "Default")
      (node (ref "R126") (pin "1") (pinfunction "1_1") (pintype "passive"))
      (node (ref "U10") (pin "5") (pinfunction "GPB3_5") (pintype "bidirectional"))
    )
    (net (code "79") (name "/NI_GP12") (class "Default")
      (node (ref "R133") (pin "1") (pinfunction "1_1") (pintype "passive"))
      (node (ref "U10") (pin "7") (pinfunction "GPB4_7") (pintype "bidirectional"))
    )
    (net (code "80") (name "/NI_GP13") (class "Default")
      (node (ref "R135") (pin "1") (pinfunction "1_1") (pintype "passive"))
      (node (ref "U10") (pin "11") (pinfunction "GPB5_11") (pintype "bidirectional"))
    )
    (net (code "81") (name "/NI_GP14") (class "Default")
      (node (ref "R136") (pin "1") (pinfunction "1_1") (pintype "passive"))
      (node (ref "U10") (pin "12") (pinfunction "GPB6_12") (pintype "bidirectional"))
    )
    (net (code "82") (name "/NI_GP15") (class "Default")
      (node (ref "R138") (pin "1") (pinfunction "1_1") (pintype "passive"))
      (node (ref "U10") (pin "13") (pinfunction "GPB7_13") (pintype "bidirectional"))
    )
    (net (code "83") (name "/VOA") (class "Default")
      (node (ref "R114") (pin "2") (pinfunction "2_2") (pintype "passive"))
      (node (ref "U11") (pin "4") (pinfunction "VOA_4") (pintype "output"))
    )
    (net (code "84") (name "/VOB") (class "Default")
      (node (ref "R116") (pin "2") (pinfunction "2_2") (pintype "passive"))
      (node (ref "U11") (pin "13") (pinfunction "VOB_13") (pintype "output"))
    )
    (net (code "85") (name "/VOC") (class "Default")
      (node (ref "R118") (pin "2") (pinfunction "2_2") (pintype "passive"))
      (node (ref "U11") (pin "5") (pinfunction "VOC_5") (pintype "output"))
    )
    (net (code "86") (name "/VOD") (class "Default")
      (node (ref "R121") (pin "2") (pinfunction "2_2") (pintype "passive"))
      (node (ref "U11") (pin "12") (pinfunction "VOD_12") (pintype "output"))
    )
    (net (code "87") (name "/VOE") (class "Default")
      (node (ref "R123") (pin "2") (pinfunction "2_2") (pintype "passive"))
      (node (ref "U11") (pin "6") (pinfunction "VOE_6") (pintype "output"))
    )
    (net (code "88") (name "/VOF") (class "Default")
      (node (ref "R125") (pin "2") (pinfunction "2_2") (pintype "passive"))
      (node (ref "U11") (pin "11") (pinfunction "VOF_11") (pintype "output"))
    )
    (net (code "89") (name "/VOG") (class "Default")
      (node (ref "R132") (pin "2") (pinfunction "2_2") (pintype "passive"))
      (node (ref "U11") (pin "7") (pinfunction "VOG_7") (pintype "output"))
    )
    (net (code "90") (name "/VOH") (class "Default")
      (node (ref "R134") (pin "2") (pinfunction "2_2") (pintype "passive"))
      (node (ref "U11") (pin "10") (pinfunction "VOH_10") (pintype "output"))
    )
    (net (code "91") (name "/VREF_1") (class "Default")
      (node (ref "J8") (pin "1") (pinfunction "1_1") (pintype "passive"))
      (node (ref "R114") (pin "1") (pinfunction "1_1") (pintype "passive"))
    )
    (net (code "92") (name "/VREF_2") (class "Default")
      (node (ref "J8") (pin "2") (pinfunction "2_2") (pintype "passive"))
      (node (ref "R116") (pin "1") (pinfunction "1_1") (pintype "passive"))
    )
    (net (code "93") (name "/VREF_3") (class "Default")
      (node (ref "J8") (pin "3") (pinfunction "3_3") (pintype "passive"))
      (node (ref "R118") (pin "1") (pinfunction "1_1") (pintype "passive"))
    )
    (net (code "94") (name "/VREF_4") (class "Default")
      (node (ref "J8") (pin "4") (pinfunction "4_4") (pintype "passive"))
      (node (ref "R121") (pin "1") (pinfunction "1_1") (pintype "passive"))
    )
    (net (code "95") (name "/VREF_5") (class "Default")
      (node (ref "J8") (pin "5") (pinfunction "5_5") (pintype "passive"))
      (node (ref "R123") (pin "1") (pinfunction "1_1") (pintype "passive"))
    )
    (net (code "96") (name "/VREF_6") (class "Default")
      (node (ref "J8") (pin "6") (pinfunction "6_6") (pintype "passive"))
      (node (ref "R125") (pin "1") (pinfunction "1_1") (pintype "passive"))
    )
    (net (code "97") (name "/VREF_7") (class "Default")
      (node (ref "J8") (pin "7") (pinfunction "7_7") (pintype "passive"))
      (node (ref "R132") (pin "1") (pinfunction "1_1") (pintype "passive"))
    )
    (net (code "98") (name "/VREF_8") (class "Default")
      (node (ref "J8") (pin "8") (pinfunction "8_8") (pintype "passive"))
      (node (ref "R134") (pin "1") (pinfunction "1_1") (pintype "passive"))
    )
    (net (code "100") (name "/V_REF1") (class "Default")
      (node (ref "R99") (pin "1") (pinfunction "1_1") (pintype "passive"))
      (node (ref "U7") (pin "10") (pinfunction "REF_10") (pintype "passive"))
    )
    (net (code "101") (name "/V_REF2") (class "Default")
      (node (ref "R103") (pin "1") (pinfunction "1_1") (pintype "passive"))
      (node (ref "U8") (pin "10") (pinfunction "REF_10") (pintype "passive"))
    )
    (net (code "102") (name "/V_REF3") (class "Default")
      (node (ref "R104") (pin "1") (pinfunction "1_1") (pintype "passive"))
      (node (ref "R108") (pin "2") (pinfunction "2_2") (pintype "passive"))
      (node (ref "U11") (pin "8") (pinfunction "VREF_8") (pintype "passive"))
    )
    (net (code "103") (name "GND_CPU") (class "Default")
      (node (ref "C33") (pin "2") (pinfunction "2_2") (pintype "passive"))
      (node (ref "C34") (pin "2") (pinfunction "2_2") (pintype "passive"))
      (node (ref "C35") (pin "2") (pinfunction "2_2") (pintype "passive"))
      (node (ref "C36") (pin "2") (pinfunction "2_2") (pintype "passive"))
      (node (ref "C37") (pin "2") (pinfunction "2_2") (pintype "passive"))
      (node (ref "C38") (pin "2") (pinfunction "2_2") (pintype "passive"))
      (node (ref "C39") (pin "2") (pinfunction "2_2") (pintype "passive"))
      (node (ref "C40") (pin "2") (pinfunction "2_2") (pintype "passive"))
      (node (ref "C41") (pin "2") (pinfunction "2_2") (pintype "passive"))
      (node (ref "C42") (pin "2") (pinfunction "2_2") (pintype "passive"))
      (node (ref "C43") (pin "2") (pinfunction "2_2") (pintype "passive"))
      (node (ref "R107") (pin "1") (pinfunction "1_1") (pintype "passive"))
      (node (ref "R108") (pin "1") (pinfunction "1_1") (pintype "passive"))
      (node (ref "R128") (pin "1") (pinfunction "1_1") (pintype "passive"))
      (node (ref "R129") (pin "1") (pinfunction "1_1") (pintype "passive"))
      (node (ref "R130") (pin "1") (pinfunction "1_1") (pintype "passive"))
      (node (ref "R131") (pin "1") (pinfunction "1_1") (pintype "passive"))
      (node (ref "R360") (pin "1") (pinfunction "1_1") (pintype "passive"))
      (node (ref "R90") (pin "1") (pinfunction "1_1") (pintype "passive"))
      (node (ref "R91") (pin "1") (pinfunction "1_1") (pintype "passive"))
      (node (ref "R92") (pin "1") (pinfunction "1_1") (pintype "passive"))
      (node (ref "U10") (pin "1") (pinfunction "Vss1_1") (pintype "passive"))
      (node (ref "U10") (pin "19") (pinfunction "Vss3_19") (pintype "passive"))
      (node (ref "U10") (pin "8") (pinfunction "Vss2_8") (pintype "passive"))
      (node (ref "U11") (pin "14") (pinfunction "GND_14") (pintype "passive"))
      (node (ref "U7") (pin "11") (pinfunction "COM_11") (pintype "passive"))
      (node (ref "U7") (pin "9") (pinfunction "GND_9") (pintype "passive"))
      (node (ref "U8") (pin "11") (pinfunction "COM_11") (pintype "passive"))
      (node (ref "U8") (pin "9") (pinfunction "GND_9") (pintype "passive"))
      (node (ref "U9") (pin "3") (pinfunction "ANODA_3") (pintype "passive"))
    )
    (net (code "104") (name "Net-(TP11-TP)") (class "Default")
      (node (ref "R106") (pin "1") (pinfunction "1_1") (pintype "passive"))
      (node (ref "TP11") (pin "1") (pinfunction "TP_1") (pintype "passive"))
      (node (ref "U10") (pin "6") (pinfunction "~{IN}T_6") (pintype "open_collector"))
    )
    (net (code "105") (name "Net-(TP12-TP)") (class "Default")
      (node (ref "TP12") (pin "1") (pinfunction "TP_1") (pintype "passive"))
      (node (ref "U10") (pin "10") (pinfunction "TP_10") (pintype "output"))
    )
    (net (code "106") (name "Net-(U9-CAT)") (class "Default")
      (node (ref "R102") (pin "2") (pinfunction "2_2") (pintype "passive"))
      (node (ref "R103") (pin "2") (pinfunction "2_2") (pintype "passive"))
      (node (ref "R104") (pin "2") (pinfunction "2_2") (pintype "passive"))
      (node (ref "R98") (pin "1") (pinfunction "1_1") (pintype "passive"))
      (node (ref "R99") (pin "2") (pinfunction "2_2") (pintype "passive"))
      (node (ref "U9") (pin "1") (pinfunction "CAT_1") (pintype "passive"))
    )
    (net (code "107") (name "Net-(U9-Vref)") (class "Default")
      (node (ref "R102") (pin "1") (pinfunction "1_1") (pintype "passive"))
      (node (ref "R107") (pin "2") (pinfunction "2_2") (pintype "passive"))
      (node (ref "U9") (pin "2") (pinfunction "Vref_2") (pintype "passive"))
    )
    (net (code "108") (name "Net-(U10-CLK)") (class "Default")
      (node (ref "C43") (pin "1") (pinfunction "1_1") (pintype "passive"))
      (node (ref "R127") (pin "1") (pinfunction "1_1") (pintype "passive"))
      (node (ref "U10") (pin "9") (pinfunction "CLK_9") (pintype "input"))
    )
  )
)
